# Ex_LED_KIT.net
KiCad netlist of a schematic drawn in EAGLE
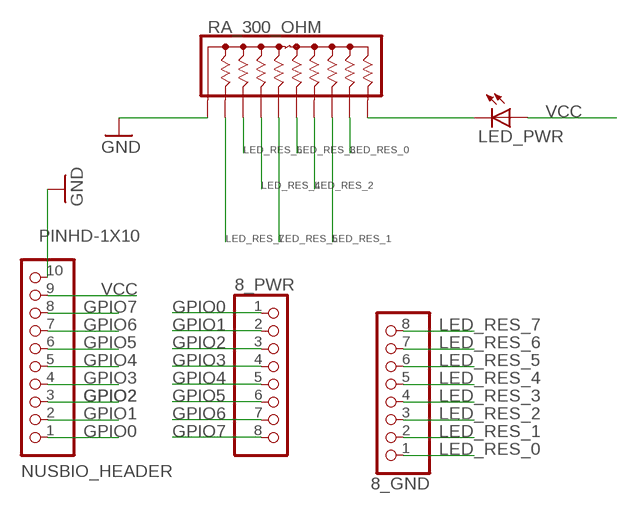
[diagram p0: schematic, sheet 1]

(export (version "E")
  (design (tool "Eeschema 10.0.6"))
  (components
    (comp (ref "8_GND")
      (value "PINHD-1X8")
      (footprint "eagle-import:1X08")
      (libsource (lib "eagle-import") (part "PINHD-1X8"))
    )
    (comp (ref "8_PWR")
      (value "PINHD-1X8")
      (footprint "eagle-import:1X08")
      (libsource (lib "eagle-import") (part "PINHD-1X8"))
    )
    (comp (ref "LED_PWR")
      (value "LEDCHIPLED_0805")
      (footprint "eagle-import:CHIPLED_0805")
      (libsource (lib "eagle-import") (part "LEDCHIPLED_0805"))
    )
    (comp (ref "NUSBIO_HEADER")
      (value "PINHD-1X10")
      (footprint "eagle-import:1X10-BIG")
      (libsource (lib "eagle-import") (part "PINHD-1X10"))
    )
    (comp (ref "RA_300_OHM")
      (value "4610X")
      (footprint "eagle-import:SIP10")
      (libsource (lib "eagle-import") (part "4610X"))
    )
  )
  (nets
    (net (code "1") (name "/GPIO0") (class "Default")
      (node (ref "8_PWR") (pin "1") (pinfunction "1_1") (pintype "passive"))
      (node (ref "NUSBIO_HEADER") (pin "1") (pinfunction "1_1") (pintype "passive"))
    )
    (net (code "2") (name "/GPIO1") (class "Default")
      (node (ref "8_PWR") (pin "2") (pinfunction "2_2") (pintype "passive"))
      (node (ref "NUSBIO_HEADER") (pin "2") (pinfunction "2_2") (pintype "passive"))
    )
    (net (code "3") (name "/GPIO2") (class "Default")
      (node (ref "8_PWR") (pin "3") (pinfunction "3_3") (pintype "passive"))
      (node (ref "NUSBIO_HEADER") (pin "3") (pinfunction "3_3") (pintype "passive"))
    )
    (net (code "4") (name "/GPIO3") (class "Default")
      (node (ref "8_PWR") (pin "4") (pinfunction "4_4") (pintype "passive"))
      (node (ref "NUSBIO_HEADER") (pin "4") (pinfunction "4_4") (pintype "passive"))
    )
    (net (code "5") (name "/GPIO4") (class "Default")
      (node (ref "8_PWR") (pin "5") (pinfunction "5_5") (pintype "passive"))
      (node (ref "NUSBIO_HEADER") (pin "5") (pinfunction "5_5") (pintype "passive"))
    )
    (net (code "6") (name "/GPIO5") (class "Default")
      (node (ref "8_PWR") (pin "6") (pinfunction "6_6") (pintype "passive"))
      (node (ref "NUSBIO_HEADER") (pin "6") (pinfunction "6_6") (pintype "passive"))
    )
    (net (code "7") (name "/GPIO6") (class "Default")
      (node (ref "8_PWR") (pin "7") (pinfunction "7_7") (pintype "passive"))
      (node (ref "NUSBIO_HEADER") (pin "7") (pinfunction "7_7") (pintype "passive"))
    )
    (net (code "8") (name "/GPIO7") (class "Default")
      (node (ref "8_PWR") (pin "8") (pinfunction "8_8") (pintype "passive"))
      (node (ref "NUSBIO_HEADER") (pin "8") (pinfunction "8_8") (pintype "passive"))
    )
    (net (code "9") (name "/LED_RES_0") (class "Default")
      (node (ref "8_GND") (pin "1") (pinfunction "1_1") (pintype "passive"))
      (node (ref "RA_300_OHM") (pin "9") (pinfunction "9_9") (pintype "passive"))
    )
    (net (code "10") (name "/LED_RES_1") (class "Default")
      (node (ref "8_GND") (pin "2") (pinfunction "2_2") (pintype "passive"))
      (node (ref "RA_300_OHM") (pin "8") (pinfunction "8_8") (pintype "passive"))
    )
    (net (code "11") (name "/LED_RES_2") (class "Default")
      (node (ref "8_GND") (pin "3") (pinfunction "3_3") (pintype "passive"))
      (node (ref "RA_300_OHM") (pin "7") (pinfunction "7_7") (pintype "passive"))
    )
    (net (code "12") (name "/LED_RES_3") (class "Default")
      (node (ref "8_GND") (pin "4") (pinfunction "4_4") (pintype "passive"))
      (node (ref "RA_300_OHM") (pin "6") (pinfunction "6_6") (pintype "passive"))
    )
    (net (code "13") (name "/LED_RES_4") (class "Default")
      (node (ref "8_GND") (pin "5") (pinfunction "5_5") (pintype "passive"))
      (node (ref "RA_300_OHM") (pin "4") (pinfunction "4_4") (pintype "passive"))
    )
    (net (code "14") (name "/LED_RES_5") (class "Default")
      (node (ref "8_GND") (pin "6") (pinfunction "6_6") (pintype "passive"))
      (node (ref "RA_300_OHM") (pin "5") (pinfunction "5_5") (pintype "passive"))
    )
    (net (code "15") (name "/LED_RES_6") (class "Default")
      (node (ref "8_GND") (pin "7") (pinfunction "7_7") (pintype "passive"))
      (node (ref "RA_300_OHM") (pin "3") (pinfunction "3_3") (pintype "passive"))
    )
    (net (code "16") (name "/LED_RES_7") (class "Default")
      (node (ref "8_GND") (pin "8") (pinfunction "8_8") (pintype "passive"))
      (node (ref "RA_300_OHM") (pin "2") (pinfunction "2_2") (pintype "passive"))
    )
    (net (code "17") (name "/VCC") (class "Default")
      (node (ref "LED_PWR") (pin "A") (pinfunction "A_A") (pintype "passive"))
      (node (ref "NUSBIO_HEADER") (pin "9") (pinfunction "9_9") (pintype "passive"))
    )
    (net (code "18") (name "GND") (class "Default")
      (node (ref "NUSBIO_HEADER") (pin "10") (pinfunction "10_10") (pintype "passive"))
      (node (ref "RA_300_OHM") (pin "1") (pinfunction "1_1") (pintype "passive"))
    )
    (net (code "19") (name "Net-(LED_PWR-PadC)") (class "Default")
      (node (ref "LED_PWR") (pin "C") (pinfunction "C_C") (pintype "passive"))
      (node (ref "RA_300_OHM") (pin "10") (pinfunction "10_10") (pintype "passive"))
    )
  )
)
